# M688B.net
KiCad netlist of a schematic drawn in EAGLE
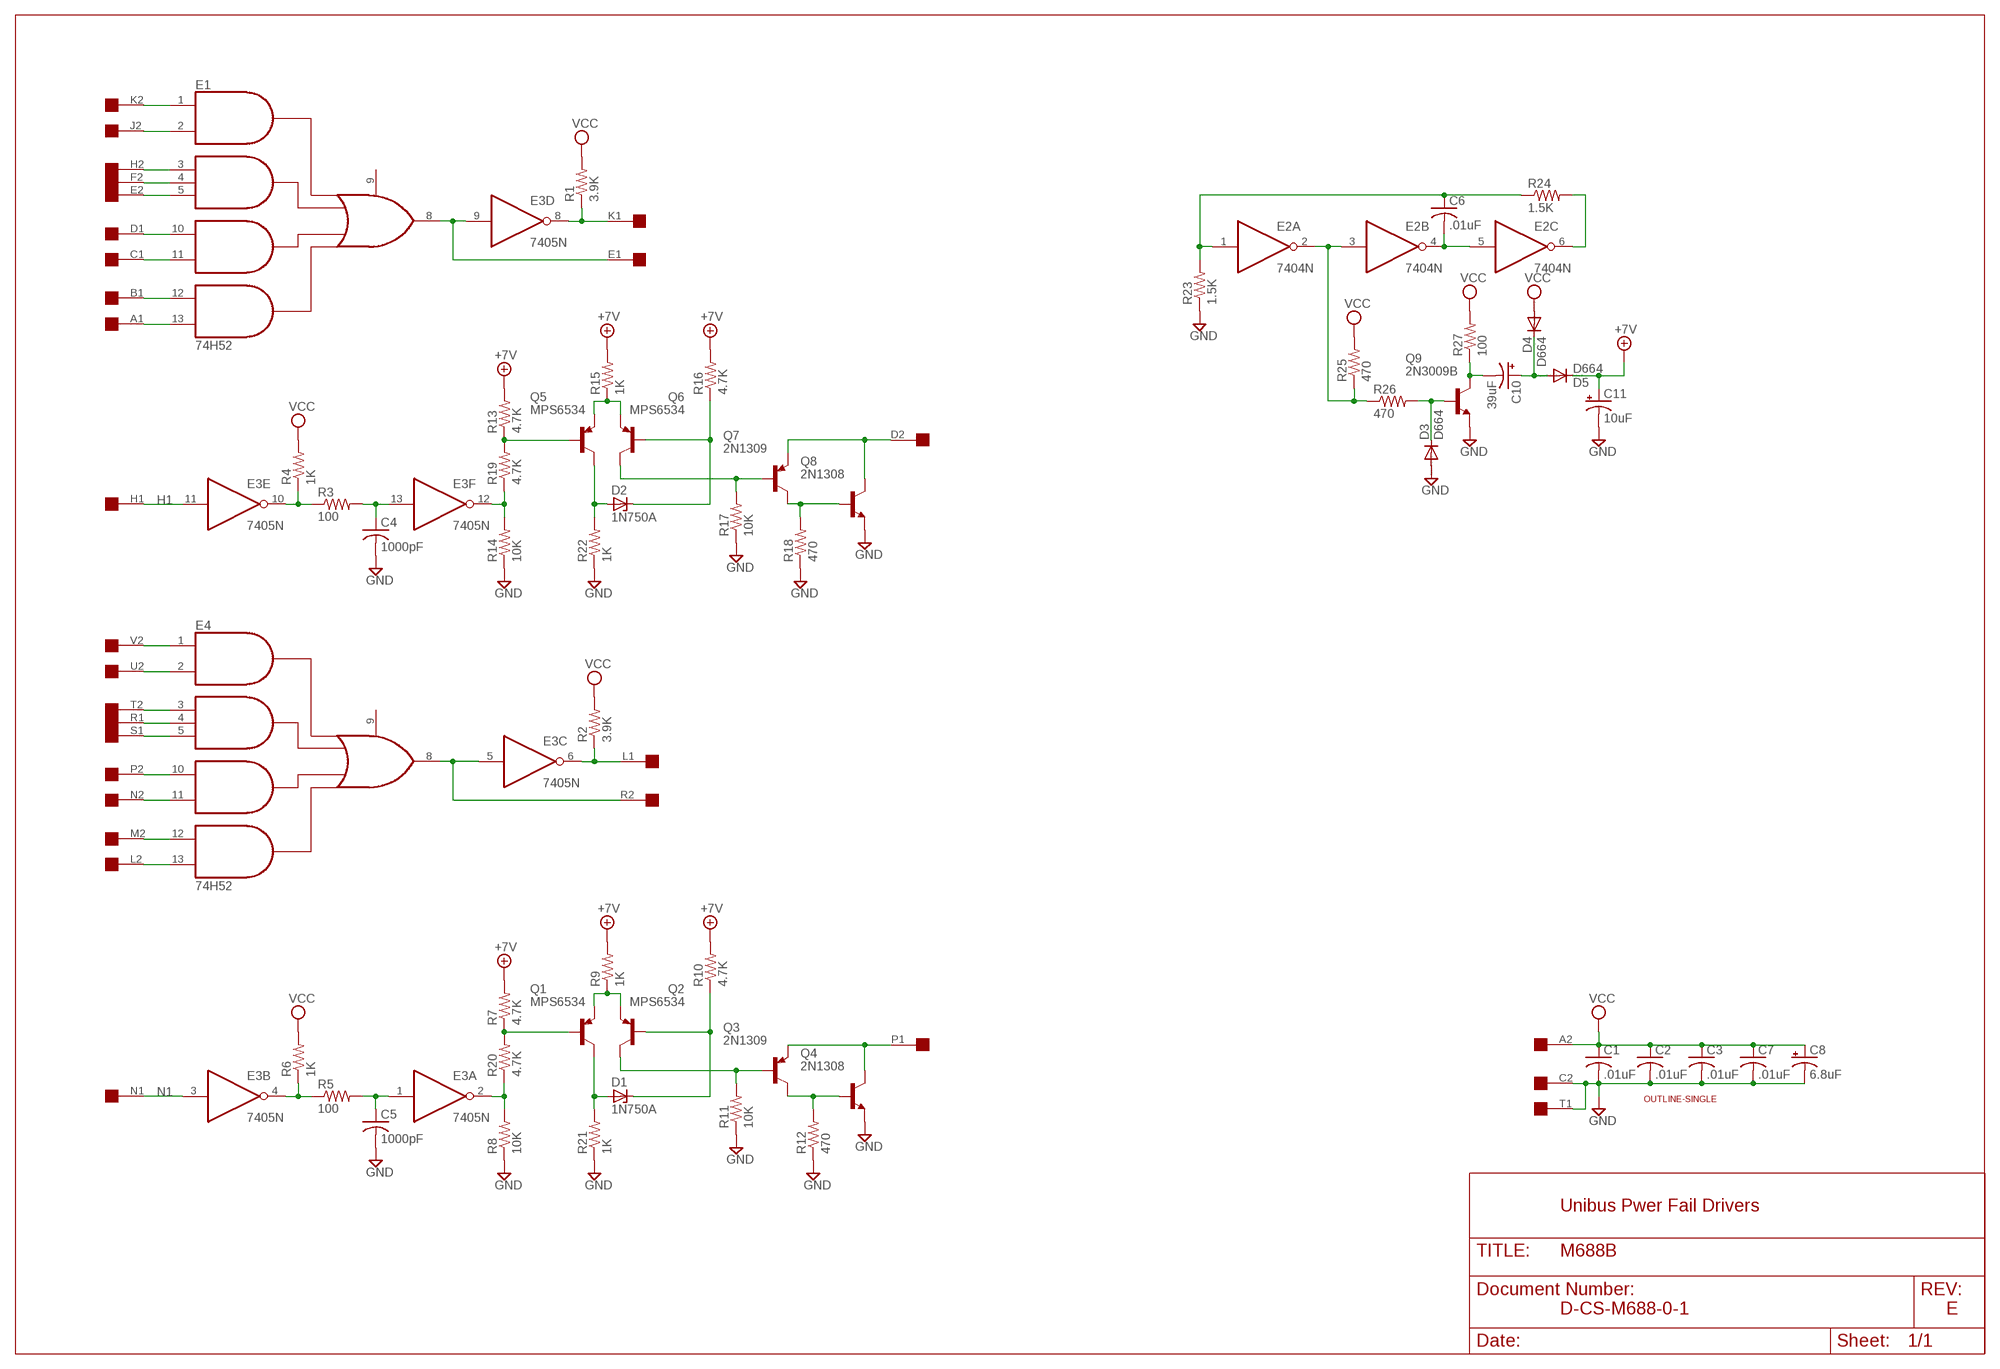
[diagram p0: schematic, sheet 1]

(export (version "E")
  (design (tool "Eeschema 10.0.6"))
  (components
    (comp (ref "C1")
      (value ".01uF")
      (footprint "eagle-import:C050-025X075")
      (libsource (lib "eagle-import") (part "C-US050-025X075"))
    )
    (comp (ref "C2")
      (value ".01uF")
      (footprint "eagle-import:C050-025X075")
      (libsource (lib "eagle-import") (part "C-US050-025X075"))
    )
    (comp (ref "C3")
      (value ".01uF")
      (footprint "eagle-import:C050-025X075")
      (libsource (lib "eagle-import") (part "C-US050-025X075"))
    )
    (comp (ref "C4")
      (value "1000pF")
      (footprint "eagle-import:C050-025X075")
      (libsource (lib "eagle-import") (part "C-US050-025X075"))
    )
    (comp (ref "C5")
      (value "1000pF")
      (footprint "eagle-import:C050-025X075")
      (libsource (lib "eagle-import") (part "C-US050-025X075"))
    )
    (comp (ref "C6")
      (value ".01uF")
      (footprint "eagle-import:C050-025X075")
      (libsource (lib "eagle-import") (part "C-US050-025X075"))
    )
    (comp (ref "C7")
      (value ".01uF")
      (footprint "eagle-import:C050-025X075")
      (libsource (lib "eagle-import") (part "C-US050-025X075"))
    )
    (comp (ref "C8")
      (value "6.8uF")
      (footprint "eagle-import:E12-8")
      (libsource (lib "eagle-import") (part "CPOL-USE20-8AXIAL"))
    )
    (comp (ref "C10")
      (value "39uF")
      (footprint "eagle-import:E12-8")
      (libsource (lib "eagle-import") (part "CPOL-USE20-8AXIAL"))
    )
    (comp (ref "C11")
      (value "10uF")
      (footprint "eagle-import:E12-8")
      (libsource (lib "eagle-import") (part "CPOL-USE20-8AXIAL"))
    )
    (comp (ref "D1")
      (value "1N750A")
      (footprint "eagle-import:DO35Z10")
      (libsource (lib "eagle-import") (part "ZENER-DIODEDO35Z10"))
    )
    (comp (ref "D2")
      (value "1N750A")
      (footprint "eagle-import:DO35Z10")
      (libsource (lib "eagle-import") (part "ZENER-DIODEDO35Z10"))
    )
    (comp (ref "D3")
      (value "D664")
      (footprint "eagle-import:DO35-10")
      (libsource (lib "eagle-import") (part "DIODE-DO35-10"))
    )
    (comp (ref "D4")
      (value "D664")
      (footprint "eagle-import:DO35-10")
      (libsource (lib "eagle-import") (part "DIODE-DO35-10"))
    )
    (comp (ref "D5")
      (value "D664")
      (footprint "eagle-import:DO35-10")
      (libsource (lib "eagle-import") (part "DIODE-DO35-10"))
    )
    (comp (ref "E1")
      (value "74H52")
      (footprint "eagle-import:DIL14")
      (libsource (lib "eagle-import") (part "7452H"))
    )
    (comp (ref "E2")
      (value "7404N")
      (footprint "eagle-import:DIL14")
      (libsource (lib "eagle-import") (part "7404N"))
    )
    (comp (ref "E3")
      (value "7405N")
      (footprint "eagle-import:DIL14")
      (libsource (lib "eagle-import") (part "7405N"))
    )
    (comp (ref "E4")
      (value "74H52")
      (footprint "eagle-import:DIL14")
      (libsource (lib "eagle-import") (part "7452H"))
    )
    (comp (ref "Q1")
      (value "MPS6534")
      (footprint "eagle-import:TO5")
      (libsource (lib "eagle-import") (part "-PNP-TO5"))
    )
    (comp (ref "Q2")
      (value "MPS6534")
      (footprint "eagle-import:TO5")
      (libsource (lib "eagle-import") (part "-PNP-TO5"))
    )
    (comp (ref "Q3")
      (value "2N1309")
      (footprint "eagle-import:TO5")
      (libsource (lib "eagle-import") (part "-PNP-TO5"))
    )
    (comp (ref "Q4")
      (value "2N1308")
      (footprint "eagle-import:TO5")
      (libsource (lib "eagle-import") (part "-NPN-TO5"))
    )
    (comp (ref "Q5")
      (value "MPS6534")
      (footprint "eagle-import:TO5")
      (libsource (lib "eagle-import") (part "-PNP-TO5"))
    )
    (comp (ref "Q6")
      (value "MPS6534")
      (footprint "eagle-import:TO5")
      (libsource (lib "eagle-import") (part "-PNP-TO5"))
    )
    (comp (ref "Q7")
      (value "2N1309")
      (footprint "eagle-import:TO5")
      (libsource (lib "eagle-import") (part "-PNP-TO5"))
    )
    (comp (ref "Q8")
      (value "2N1308")
      (footprint "eagle-import:TO5")
      (libsource (lib "eagle-import") (part "-NPN-TO5"))
    )
    (comp (ref "Q9")
      (value "2N3009B")
      (footprint "eagle-import:TO5")
      (libsource (lib "eagle-import") (part "-NPN-TO5"))
    )
    (comp (ref "R1")
      (value "3.9K")
      (footprint "eagle-import:0207_10")
      (libsource (lib "eagle-import") (part "R-US_0207/10"))
    )
    (comp (ref "R2")
      (value "3.9K")
      (footprint "eagle-import:0207_10")
      (libsource (lib "eagle-import") (part "R-US_0207/10"))
    )
    (comp (ref "R3")
      (value "100")
      (footprint "eagle-import:0207_10")
      (libsource (lib "eagle-import") (part "R-US_0207/10"))
    )
    (comp (ref "R4")
      (value "1K")
      (footprint "eagle-import:0207_10")
      (libsource (lib "eagle-import") (part "R-US_0207/10"))
    )
    (comp (ref "R5")
      (value "100")
      (footprint "eagle-import:0207_10")
      (libsource (lib "eagle-import") (part "R-US_0207/10"))
    )
    (comp (ref "R6")
      (value "1K")
      (footprint "eagle-import:0207_10")
      (libsource (lib "eagle-import") (part "R-US_0207/10"))
    )
    (comp (ref "R7")
      (value "4.7K")
      (footprint "eagle-import:0207_10")
      (libsource (lib "eagle-import") (part "R-US_0207/10"))
    )
    (comp (ref "R8")
      (value "10K")
      (footprint "eagle-import:0207_10")
      (libsource (lib "eagle-import") (part "R-US_0207/10"))
    )
    (comp (ref "R9")
      (value "1K")
      (footprint "eagle-import:0207_10")
      (libsource (lib "eagle-import") (part "R-US_0207/10"))
    )
    (comp (ref "R10")
      (value "4.7K")
      (footprint "eagle-import:0207_10")
      (libsource (lib "eagle-import") (part "R-US_0207/10"))
    )
    (comp (ref "R11")
      (value "10K")
      (footprint "eagle-import:0207_10")
      (libsource (lib "eagle-import") (part "R-US_0207/10"))
    )
    (comp (ref "R12")
      (value "470")
      (footprint "eagle-import:0207_10")
      (libsource (lib "eagle-import") (part "R-US_0207/10"))
    )
    (comp (ref "R13")
      (value "4.7K")
      (footprint "eagle-import:0207_10")
      (libsource (lib "eagle-import") (part "R-US_0207/10"))
    )
    (comp (ref "R14")
      (value "10K")
      (footprint "eagle-import:0207_10")
      (libsource (lib "eagle-import") (part "R-US_0207/10"))
    )
    (comp (ref "R15")
      (value "1K")
      (footprint "eagle-import:0207_10")
      (libsource (lib "eagle-import") (part "R-US_0207/10"))
    )
    (comp (ref "R16")
      (value "4.7K")
      (footprint "eagle-import:0207_10")
      (libsource (lib "eagle-import") (part "R-US_0207/10"))
    )
    (comp (ref "R17")
      (value "10K")
      (footprint "eagle-import:0207_10")
      (libsource (lib "eagle-import") (part "R-US_0207/10"))
    )
    (comp (ref "R18")
      (value "470")
      (footprint "eagle-import:0207_10")
      (libsource (lib "eagle-import") (part "R-US_0207/10"))
    )
    (comp (ref "R19")
      (value "4.7K")
      (footprint "eagle-import:0207_10")
      (libsource (lib "eagle-import") (part "R-US_0207/10"))
    )
    (comp (ref "R20")
      (value "4.7K")
      (footprint "eagle-import:0207_10")
      (libsource (lib "eagle-import") (part "R-US_0207/10"))
    )
    (comp (ref "R21")
      (value "1K")
      (footprint "eagle-import:0207_10")
      (libsource (lib "eagle-import") (part "R-US_0207/10"))
    )
    (comp (ref "R22")
      (value "1K")
      (footprint "eagle-import:0207_10")
      (libsource (lib "eagle-import") (part "R-US_0207/10"))
    )
    (comp (ref "R23")
      (value "1.5K")
      (footprint "eagle-import:0207_10")
      (libsource (lib "eagle-import") (part "R-US_0207/10"))
    )
    (comp (ref "R24")
      (value "1.5K")
      (footprint "eagle-import:0207_10")
      (libsource (lib "eagle-import") (part "R-US_0207/10"))
    )
    (comp (ref "R25")
      (value "470")
      (footprint "eagle-import:0207_10")
      (libsource (lib "eagle-import") (part "R-US_0207/10"))
    )
    (comp (ref "R26")
      (value "470")
      (footprint "eagle-import:0207_10")
      (libsource (lib "eagle-import") (part "R-US_0207/10"))
    )
    (comp (ref "R27")
      (value "100")
      (footprint "eagle-import:0207_10")
      (libsource (lib "eagle-import") (part "R-US_0207/10"))
    )
    (comp (ref "U$1")
      (value "OUTLINE-SINGLE")
      (footprint "eagle-import:SINGLE")
      (libsource (lib "eagle-import") (part "OUTLINE-SINGLE"))
    )
    (comp (ref "U$2")
      (value "SINGLE")
      (footprint "eagle-import:EDGE-CON2")
      (libsource (lib "eagle-import") (part "SINGLE"))
    )
  )
  (nets
    (net (code "1") (name "+7V") (class "Default")
      (node (ref "C11") (pin "+") (pinfunction "+_+") (pintype "passive"))
      (node (ref "D5") (pin "C") (pinfunction "C_C") (pintype "passive"))
      (node (ref "R10") (pin "2") (pinfunction "2_2") (pintype "passive"))
      (node (ref "R13") (pin "2") (pinfunction "2_2") (pintype "passive"))
      (node (ref "R15") (pin "2") (pinfunction "2_2") (pintype "passive"))
      (node (ref "R16") (pin "2") (pinfunction "2_2") (pintype "passive"))
      (node (ref "R7") (pin "2") (pinfunction "2_2") (pintype "passive"))
      (node (ref "R9") (pin "2") (pinfunction "2_2") (pintype "passive"))
    )
    (net (code "2") (name "/H1") (class "Default")
      (node (ref "E3") (pin "11") (pinfunction "I_11") (pintype "input"))
      (node (ref "U$2") (pin "H1") (pinfunction "1_H1") (pintype "bidirectional"))
    )
    (net (code "3") (name "/N1") (class "Default")
      (node (ref "E3") (pin "3") (pinfunction "I_3") (pintype "input"))
      (node (ref "U$2") (pin "N1") (pinfunction "1_N1") (pintype "bidirectional"))
    )
    (net (code "4") (name "GND") (class "Default")
      (node (ref "C1") (pin "2") (pinfunction "2_2") (pintype "passive"))
      (node (ref "C11") (pin "-") (pinfunction "-_-") (pintype "passive"))
      (node (ref "C2") (pin "2") (pinfunction "2_2") (pintype "passive"))
      (node (ref "C3") (pin "2") (pinfunction "2_2") (pintype "passive"))
      (node (ref "C4") (pin "2") (pinfunction "2_2") (pintype "passive"))
      (node (ref "C5") (pin "2") (pinfunction "2_2") (pintype "passive"))
      (node (ref "C7") (pin "2") (pinfunction "2_2") (pintype "passive"))
      (node (ref "C8") (pin "-") (pinfunction "-_-") (pintype "passive"))
      (node (ref "D3") (pin "A") (pinfunction "A_A") (pintype "passive"))
      (node (ref "Q4") (pin "1") (pinfunction "E_1") (pintype "passive"))
      (node (ref "Q8") (pin "1") (pinfunction "E_1") (pintype "passive"))
      (node (ref "Q9") (pin "1") (pinfunction "E_1") (pintype "passive"))
      (node (ref "R11") (pin "1") (pinfunction "1_1") (pintype "passive"))
      (node (ref "R12") (pin "1") (pinfunction "1_1") (pintype "passive"))
      (node (ref "R14") (pin "1") (pinfunction "1_1") (pintype "passive"))
      (node (ref "R17") (pin "1") (pinfunction "1_1") (pintype "passive"))
      (node (ref "R18") (pin "1") (pinfunction "1_1") (pintype "passive"))
      (node (ref "R21") (pin "1") (pinfunction "1_1") (pintype "passive"))
      (node (ref "R22") (pin "1") (pinfunction "1_1") (pintype "passive"))
      (node (ref "R23") (pin "1") (pinfunction "1_1") (pintype "passive"))
      (node (ref "R8") (pin "1") (pinfunction "1_1") (pintype "passive"))
      (node (ref "U$2") (pin "C2") (pinfunction "1_C2") (pintype "bidirectional"))
      (node (ref "U$2") (pin "T1") (pinfunction "1_T1") (pintype "bidirectional"))
    )
    (net (code "5") (name "Net-(C10-Pad+)") (class "Default")
      (node (ref "C10") (pin "+") (pinfunction "+_+") (pintype "passive"))
      (node (ref "D4") (pin "C") (pinfunction "C_C") (pintype "passive"))
      (node (ref "D5") (pin "A") (pinfunction "A_A") (pintype "passive"))
    )
    (net (code "6") (name "Net-(E1A-I1)") (class "Default")
      (node (ref "E1") (pin "1") (pinfunction "I1_1") (pintype "input"))
      (node (ref "U$2") (pin "K2") (pinfunction "1_K2") (pintype "bidirectional"))
    )
    (net (code "7") (name "Net-(E1A-I2)") (class "Default")
      (node (ref "E1") (pin "2") (pinfunction "I2_2") (pintype "input"))
      (node (ref "U$2") (pin "J2") (pinfunction "1_J2") (pintype "bidirectional"))
    )
    (net (code "8") (name "Net-(E1A-I3)") (class "Default")
      (node (ref "E1") (pin "3") (pinfunction "I3_3") (pintype "input"))
      (node (ref "U$2") (pin "H2") (pinfunction "1_H2") (pintype "bidirectional"))
    )
    (net (code "9") (name "Net-(E1A-I4)") (class "Default")
      (node (ref "E1") (pin "4") (pinfunction "I4_4") (pintype "input"))
      (node (ref "U$2") (pin "F2") (pinfunction "1_F2") (pintype "bidirectional"))
    )
    (net (code "10") (name "Net-(E1A-I5)") (class "Default")
      (node (ref "E1") (pin "5") (pinfunction "I5_5") (pintype "input"))
      (node (ref "U$2") (pin "E2") (pinfunction "1_E2") (pintype "bidirectional"))
    )
    (net (code "11") (name "Net-(E1A-I10)") (class "Default")
      (node (ref "E1") (pin "10") (pinfunction "I10_10") (pintype "input"))
      (node (ref "U$2") (pin "D1") (pinfunction "1_D1") (pintype "bidirectional"))
    )
    (net (code "12") (name "Net-(E1A-I11)") (class "Default")
      (node (ref "E1") (pin "11") (pinfunction "I11_11") (pintype "input"))
      (node (ref "U$2") (pin "C1") (pinfunction "1_C1") (pintype "bidirectional"))
    )
    (net (code "13") (name "Net-(E1A-I12)") (class "Default")
      (node (ref "E1") (pin "12") (pinfunction "I12_12") (pintype "input"))
      (node (ref "U$2") (pin "B1") (pinfunction "1_B1") (pintype "bidirectional"))
    )
    (net (code "14") (name "Net-(E1A-I13)") (class "Default")
      (node (ref "E1") (pin "13") (pinfunction "I13_13") (pintype "input"))
      (node (ref "U$2") (pin "A1") (pinfunction "1_A1") (pintype "bidirectional"))
    )
    (net (code "15") (name "Net-(E1A-O8)") (class "Default")
      (node (ref "E1") (pin "8") (pinfunction "O8_8") (pintype "output"))
      (node (ref "E3") (pin "9") (pinfunction "I_9") (pintype "input"))
      (node (ref "U$2") (pin "E1") (pinfunction "1_E1") (pintype "bidirectional"))
    )
    (net (code "16") (name "Net-(E2A-I)") (class "Default")
      (node (ref "C6") (pin "1") (pinfunction "1_1") (pintype "passive"))
      (node (ref "E2") (pin "1") (pinfunction "I_1") (pintype "input"))
      (node (ref "R23") (pin "2") (pinfunction "2_2") (pintype "passive"))
      (node (ref "R24") (pin "1") (pinfunction "1_1") (pintype "passive"))
    )
    (net (code "17") (name "Net-(E2A-O)") (class "Default")
      (node (ref "E2") (pin "2") (pinfunction "O_2") (pintype "output"))
      (node (ref "E2") (pin "3") (pinfunction "I_3") (pintype "input"))
      (node (ref "R25") (pin "1") (pinfunction "1_1") (pintype "passive"))
      (node (ref "R26") (pin "1") (pinfunction "1_1") (pintype "passive"))
    )
    (net (code "18") (name "Net-(E2B-O)") (class "Default")
      (node (ref "C6") (pin "2") (pinfunction "2_2") (pintype "passive"))
      (node (ref "E2") (pin "4") (pinfunction "O_4") (pintype "output"))
      (node (ref "E2") (pin "5") (pinfunction "I_5") (pintype "input"))
    )
    (net (code "19") (name "Net-(E2C-O)") (class "Default")
      (node (ref "E2") (pin "6") (pinfunction "O_6") (pintype "output"))
      (node (ref "R24") (pin "2") (pinfunction "2_2") (pintype "passive"))
    )
    (net (code "20") (name "Net-(E3A-I)") (class "Default")
      (node (ref "C5") (pin "1") (pinfunction "1_1") (pintype "passive"))
      (node (ref "E3") (pin "1") (pinfunction "I_1") (pintype "input"))
      (node (ref "R5") (pin "2") (pinfunction "2_2") (pintype "passive"))
    )
    (net (code "21") (name "Net-(E3A-O)") (class "Default")
      (node (ref "E3") (pin "2") (pinfunction "O_2") (pintype "open_collector"))
      (node (ref "R20") (pin "1") (pinfunction "1_1") (pintype "passive"))
      (node (ref "R8") (pin "2") (pinfunction "2_2") (pintype "passive"))
    )
    (net (code "22") (name "Net-(E3B-O)") (class "Default")
      (node (ref "E3") (pin "4") (pinfunction "O_4") (pintype "open_collector"))
      (node (ref "R5") (pin "1") (pinfunction "1_1") (pintype "passive"))
      (node (ref "R6") (pin "1") (pinfunction "1_1") (pintype "passive"))
    )
    (net (code "23") (name "Net-(E3C-I)") (class "Default")
      (node (ref "E3") (pin "5") (pinfunction "I_5") (pintype "input"))
      (node (ref "E4") (pin "8") (pinfunction "O8_8") (pintype "output"))
      (node (ref "U$2") (pin "R2") (pinfunction "1_R2") (pintype "bidirectional"))
    )
    (net (code "24") (name "Net-(E3C-O)") (class "Default")
      (node (ref "E3") (pin "6") (pinfunction "O_6") (pintype "open_collector"))
      (node (ref "R2") (pin "1") (pinfunction "1_1") (pintype "passive"))
      (node (ref "U$2") (pin "L1") (pinfunction "1_L1") (pintype "bidirectional"))
    )
    (net (code "25") (name "Net-(E3D-O)") (class "Default")
      (node (ref "E3") (pin "8") (pinfunction "O_8") (pintype "open_collector"))
      (node (ref "R1") (pin "1") (pinfunction "1_1") (pintype "passive"))
      (node (ref "U$2") (pin "K1") (pinfunction "1_K1") (pintype "bidirectional"))
    )
    (net (code "26") (name "Net-(E3E-O)") (class "Default")
      (node (ref "E3") (pin "10") (pinfunction "O_10") (pintype "open_collector"))
      (node (ref "R3") (pin "1") (pinfunction "1_1") (pintype "passive"))
      (node (ref "R4") (pin "1") (pinfunction "1_1") (pintype "passive"))
    )
    (net (code "27") (name "Net-(E3F-I)") (class "Default")
      (node (ref "C4") (pin "1") (pinfunction "1_1") (pintype "passive"))
      (node (ref "E3") (pin "13") (pinfunction "I_13") (pintype "input"))
      (node (ref "R3") (pin "2") (pinfunction "2_2") (pintype "passive"))
    )
    (net (code "28") (name "Net-(E3F-O)") (class "Default")
      (node (ref "E3") (pin "12") (pinfunction "O_12") (pintype "open_collector"))
      (node (ref "R14") (pin "2") (pinfunction "2_2") (pintype "passive"))
      (node (ref "R19") (pin "1") (pinfunction "1_1") (pintype "passive"))
    )
    (net (code "29") (name "Net-(E4A-I1)") (class "Default")
      (node (ref "E4") (pin "1") (pinfunction "I1_1") (pintype "input"))
      (node (ref "U$2") (pin "V2") (pinfunction "1_V2") (pintype "bidirectional"))
    )
    (net (code "30") (name "Net-(E4A-I2)") (class "Default")
      (node (ref "E4") (pin "2") (pinfunction "I2_2") (pintype "input"))
      (node (ref "U$2") (pin "U2") (pinfunction "1_U2") (pintype "bidirectional"))
    )
    (net (code "31") (name "Net-(E4A-I3)") (class "Default")
      (node (ref "E4") (pin "3") (pinfunction "I3_3") (pintype "input"))
      (node (ref "U$2") (pin "T2") (pinfunction "1_T2") (pintype "bidirectional"))
    )
    (net (code "32") (name "Net-(E4A-I4)") (class "Default")
      (node (ref "E4") (pin "4") (pinfunction "I4_4") (pintype "input"))
      (node (ref "U$2") (pin "R1") (pinfunction "1_R1") (pintype "bidirectional"))
    )
    (net (code "33") (name "Net-(E4A-I5)") (class "Default")
      (node (ref "E4") (pin "5") (pinfunction "I5_5") (pintype "input"))
      (node (ref "U$2") (pin "S1") (pinfunction "1_S1") (pintype "bidirectional"))
    )
    (net (code "34") (name "Net-(E4A-I10)") (class "Default")
      (node (ref "E4") (pin "10") (pinfunction "I10_10") (pintype "input"))
      (node (ref "U$2") (pin "P2") (pinfunction "1_P2") (pintype "bidirectional"))
    )
    (net (code "35") (name "Net-(E4A-I11)") (class "Default")
      (node (ref "E4") (pin "11") (pinfunction "I11_11") (pintype "input"))
      (node (ref "U$2") (pin "N2") (pinfunction "1_N2") (pintype "bidirectional"))
    )
    (net (code "36") (name "Net-(E4A-I12)") (class "Default")
      (node (ref "E4") (pin "12") (pinfunction "I12_12") (pintype "input"))
      (node (ref "U$2") (pin "M2") (pinfunction "1_M2") (pintype "bidirectional"))
    )
    (net (code "37") (name "Net-(E4A-I13)") (class "Default")
      (node (ref "E4") (pin "13") (pinfunction "I13_13") (pintype "input"))
      (node (ref "U$2") (pin "L2") (pinfunction "1_L2") (pintype "bidirectional"))
    )
    (net (code "38") (name "Net-(Q1-B)") (class "Default")
      (node (ref "Q1") (pin "2") (pinfunction "B_2") (pintype "passive"))
      (node (ref "R20") (pin "2") (pinfunction "2_2") (pintype "passive"))
      (node (ref "R7") (pin "1") (pinfunction "1_1") (pintype "passive"))
    )
    (net (code "39") (name "Net-(Q1-C)") (class "Default")
      (node (ref "D1") (pin "A") (pinfunction "A_A") (pintype "passive"))
      (node (ref "Q1") (pin "3") (pinfunction "C_3") (pintype "passive"))
      (node (ref "R21") (pin "2") (pinfunction "2_2") (pintype "passive"))
    )
    (net (code "40") (name "Net-(Q1-E)") (class "Default")
      (node (ref "Q1") (pin "1") (pinfunction "E_1") (pintype "passive"))
      (node (ref "Q2") (pin "1") (pinfunction "E_1") (pintype "passive"))
      (node (ref "R9") (pin "1") (pinfunction "1_1") (pintype "passive"))
    )
    (net (code "41") (name "Net-(Q2-B)") (class "Default")
      (node (ref "D1") (pin "C") (pinfunction "C_C") (pintype "passive"))
      (node (ref "Q2") (pin "2") (pinfunction "B_2") (pintype "passive"))
      (node (ref "R10") (pin "1") (pinfunction "1_1") (pintype "passive"))
    )
    (net (code "42") (name "Net-(Q2-C)") (class "Default")
      (node (ref "Q2") (pin "3") (pinfunction "C_3") (pintype "passive"))
      (node (ref "Q3") (pin "2") (pinfunction "B_2") (pintype "passive"))
      (node (ref "R11") (pin "2") (pinfunction "2_2") (pintype "passive"))
    )
    (net (code "43") (name "Net-(Q3-C)") (class "Default")
      (node (ref "Q3") (pin "3") (pinfunction "C_3") (pintype "passive"))
      (node (ref "Q4") (pin "2") (pinfunction "B_2") (pintype "passive"))
      (node (ref "R12") (pin "2") (pinfunction "2_2") (pintype "passive"))
    )
    (net (code "44") (name "Net-(Q3-E)") (class "Default")
      (node (ref "Q3") (pin "1") (pinfunction "E_1") (pintype "passive"))
      (node (ref "Q4") (pin "3") (pinfunction "C_3") (pintype "passive"))
      (node (ref "U$2") (pin "P1") (pinfunction "1_P1") (pintype "bidirectional"))
    )
    (net (code "45") (name "Net-(Q5-B)") (class "Default")
      (node (ref "Q5") (pin "2") (pinfunction "B_2") (pintype "passive"))
      (node (ref "R13") (pin "1") (pinfunction "1_1") (pintype "passive"))
      (node (ref "R19") (pin "2") (pinfunction "2_2") (pintype "passive"))
    )
    (net (code "46") (name "Net-(Q5-C)") (class "Default")
      (node (ref "D2") (pin "A") (pinfunction "A_A") (pintype "passive"))
      (node (ref "Q5") (pin "3") (pinfunction "C_3") (pintype "passive"))
      (node (ref "R22") (pin "2") (pinfunction "2_2") (pintype "passive"))
    )
    (net (code "47") (name "Net-(Q5-E)") (class "Default")
      (node (ref "Q5") (pin "1") (pinfunction "E_1") (pintype "passive"))
      (node (ref "Q6") (pin "1") (pinfunction "E_1") (pintype "passive"))
      (node (ref "R15") (pin "1") (pinfunction "1_1") (pintype "passive"))
    )
    (net (code "48") (name "Net-(Q6-B)") (class "Default")
      (node (ref "D2") (pin "C") (pinfunction "C_C") (pintype "passive"))
      (node (ref "Q6") (pin "2") (pinfunction "B_2") (pintype "passive"))
      (node (ref "R16") (pin "1") (pinfunction "1_1") (pintype "passive"))
    )
    (net (code "49") (name "Net-(Q6-C)") (class "Default")
      (node (ref "Q6") (pin "3") (pinfunction "C_3") (pintype "passive"))
      (node (ref "Q7") (pin "2") (pinfunction "B_2") (pintype "passive"))
      (node (ref "R17") (pin "2") (pinfunction "2_2") (pintype "passive"))
    )
    (net (code "50") (name "Net-(Q7-C)") (class "Default")
      (node (ref "Q7") (pin "3") (pinfunction "C_3") (pintype "passive"))
      (node (ref "Q8") (pin "2") (pinfunction "B_2") (pintype "passive"))
      (node (ref "R18") (pin "2") (pinfunction "2_2") (pintype "passive"))
    )
    (net (code "51") (name "Net-(Q7-E)") (class "Default")
      (node (ref "Q7") (pin "1") (pinfunction "E_1") (pintype "passive"))
      (node (ref "Q8") (pin "3") (pinfunction "C_3") (pintype "passive"))
      (node (ref "U$2") (pin "D2") (pinfunction "1_D2") (pintype "bidirectional"))
    )
    (net (code "52") (name "Net-(Q9-B)") (class "Default")
      (node (ref "D3") (pin "C") (pinfunction "C_C") (pintype "passive"))
      (node (ref "Q9") (pin "2") (pinfunction "B_2") (pintype "passive"))
      (node (ref "R26") (pin "2") (pinfunction "2_2") (pintype "passive"))
    )
    (net (code "53") (name "Net-(Q9-C)") (class "Default")
      (node (ref "C10") (pin "-") (pinfunction "-_-") (pintype "passive"))
      (node (ref "Q9") (pin "3") (pinfunction "C_3") (pintype "passive"))
      (node (ref "R27") (pin "1") (pinfunction "1_1") (pintype "passive"))
    )
    (net (code "54") (name "VCC") (class "Default")
      (node (ref "C1") (pin "1") (pinfunction "1_1") (pintype "passive"))
      (node (ref "C2") (pin "1") (pinfunction "1_1") (pintype "passive"))
      (node (ref "C3") (pin "1") (pinfunction "1_1") (pintype "passive"))
      (node (ref "C7") (pin "1") (pinfunction "1_1") (pintype "passive"))
      (node (ref "C8") (pin "+") (pinfunction "+_+") (pintype "passive"))
      (node (ref "D4") (pin "A") (pinfunction "A_A") (pintype "passive"))
      (node (ref "R1") (pin "2") (pinfunction "2_2") (pintype "passive"))
      (node (ref "R2") (pin "2") (pinfunction "2_2") (pintype "passive"))
      (node (ref "R25") (pin "2") (pinfunction "2_2") (pintype "passive"))
      (node (ref "R27") (pin "2") (pinfunction "2_2") (pintype "passive"))
      (node (ref "R4") (pin "2") (pinfunction "2_2") (pintype "passive"))
      (node (ref "R6") (pin "2") (pinfunction "2_2") (pintype "passive"))
      (node (ref "U$2") (pin "A2") (pinfunction "1_A2") (pintype "bidirectional"))
    )
    (net (code "55") (name "unconnected-(E1A-I9-Pad9)") (class "Default")
      (node (ref "E1") (pin "9") (pinfunction "I9_9") (pintype "passive"))
    )
    (net (code "56") (name "unconnected-(E4A-I9-Pad9)") (class "Default")
      (node (ref "E4") (pin "9") (pinfunction "I9_9") (pintype "passive"))
    )
  )
)
